# discharge-tsmp.net
KiCad netlist of a schematic drawn in Altium Designer
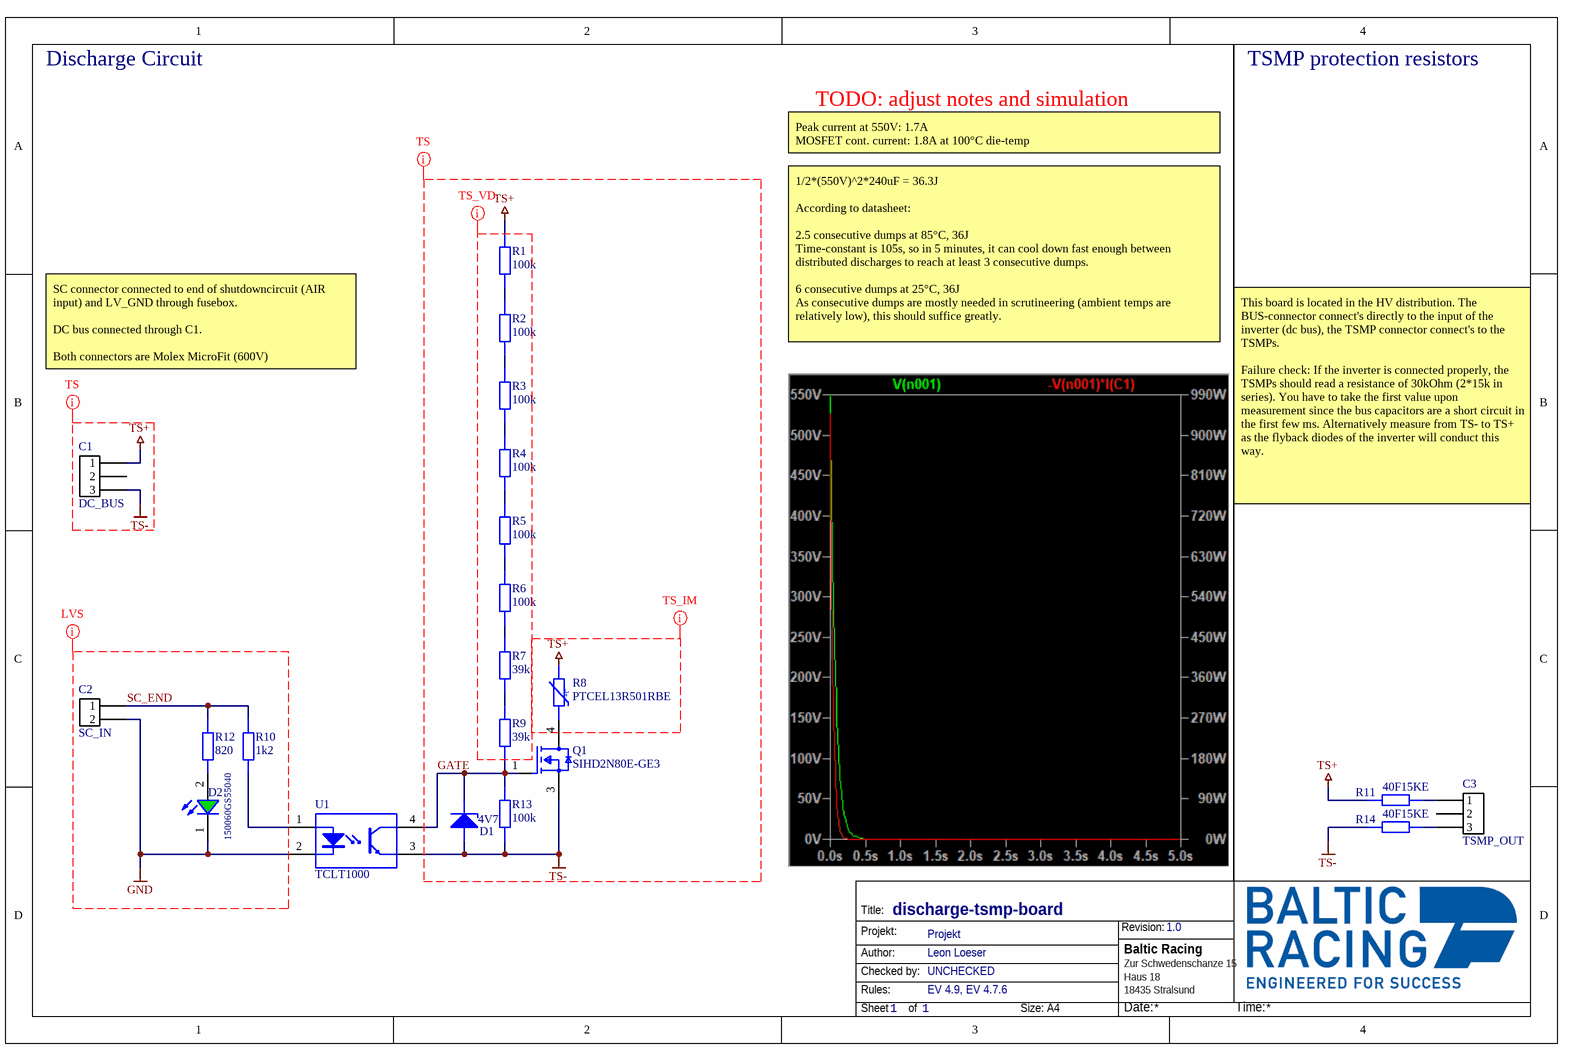
[diagram p0: discharge-tsmp.SchDoc]

(export (version "E")
  (design (tool "Eeschema 10.0.6"))
  (components
    (comp (ref "C1")
      (value "DC_BUS")
      (footprint "43650-0309")
      (description "Molex Micro-Fit 3.0 3-Pin\r\n600V\r\n8.5A")
      (libsource (lib "Standardbauteile") (part "MicroFit3.0 3-Pin"))
    )
    (comp (ref "C2")
      (value "SC_IN")
      (footprint "43650-0200")
      (description "Molex Micro-Fit 3.0 2-Pin\r\n600V\r\n8.5A")
      (libsource (lib "Standardbauteile") (part "MicroFit3.0 2-Pin"))
    )
    (comp (ref "C3")
      (value "TSMP_OUT")
      (footprint "43650-0309")
      (description "Molex Micro-Fit 3.0 3-Pin\r\n600V\r\n8.5A")
      (libsource (lib "Standardbauteile") (part "MicroFit3.0 3-Pin"))
    )
    (comp (ref "D1")
      (value "4V7")
      (footprint "SOT23")
      (libsource (lib "Standardbauteile") (part "SMD Zener Diode"))
    )
    (comp (ref "D2")
      (value "150060GS55040")
      (footprint "WL-SMCW_0603_H=0.7")
      (description "SMT Mono-color Chip LED Waterclear WL-SMCW, size 0603, Green, 3.2 V, 140 deg, 430 mcd")
      (fields (field (name "PART NUMBER") "150060GS75000") (field (name "PUBLISHER") "Wurth Elektronik"))
      (libsource (lib "ALTIUM-WL-SMCW-rev18c") (part "150060GS75000"))
    )
    (comp (ref "Q1")
      (value "SIHD2N80E-GE3")
      (footprint "FP-T16-0236-MFG")
      (description "MOSFET N-CH 800V 2.8A DPAK")
      (fields
        (field (name "MANUFACTURER") "Vishay")
        (field (name "OCTOPART") "https://octopart.com/sihd2n80e-ge3-vishay-84840963")
      )
      (libsource (lib "Altium Content Vault") (part "86656c45bbbddc162aead764a772c09"))
    )
    (comp (ref "R1")
      (value "100k")
      (footprint "STACKPOLE CSR1206")
      (description "Resistor with multiple footprints")
      (fields (field (name "Comment") "SMD Resistor"))
      (libsource (lib "Standardbauteile") (part "SMD Resistor"))
    )
    (comp (ref "R2")
      (value "100k")
      (footprint "STACKPOLE CSR1206")
      (description "Resistor with multiple footprints")
      (fields (field (name "Comment") "SMD Resistor"))
      (libsource (lib "Standardbauteile") (part "SMD Resistor"))
    )
    (comp (ref "R3")
      (value "100k")
      (footprint "STACKPOLE CSR1206")
      (description "Resistor with multiple footprints")
      (fields (field (name "Comment") "SMD Resistor"))
      (libsource (lib "Standardbauteile") (part "SMD Resistor"))
    )
    (comp (ref "R4")
      (value "100k")
      (footprint "STACKPOLE CSR1206")
      (description "Resistor with multiple footprints")
      (fields (field (name "Comment") "SMD Resistor"))
      (libsource (lib "Standardbauteile") (part "SMD Resistor"))
    )
    (comp (ref "R5")
      (value "100k")
      (footprint "STACKPOLE CSR1206")
      (description "Resistor with multiple footprints")
      (fields (field (name "Comment") "SMD Resistor"))
      (libsource (lib "Standardbauteile") (part "SMD Resistor"))
    )
    (comp (ref "R6")
      (value "100k")
      (footprint "STACKPOLE CSR1206")
      (description "Resistor with multiple footprints")
      (fields (field (name "Comment") "SMD Resistor"))
      (libsource (lib "Standardbauteile") (part "SMD Resistor"))
    )
    (comp (ref "R7")
      (value "39k")
      (footprint "STACKPOLE CSR1206")
      (description "Resistor with multiple footprints")
      (fields (field (name "Comment") "SMD Resistor"))
      (libsource (lib "Standardbauteile") (part "SMD Resistor"))
    )
    (comp (ref "R8")
      (value "PTCEL13R501RBE")
      (footprint "PTCEL13_H")
      (description "PTC Thermistors, Inrush Current Limiter and Energy Load-Dump\r\n\r\n500Ohm, 150J")
      (fields (field (name "MANUFACTURER") "Vishay"))
      (libsource (lib "Leon") (part "PTCEL13R501RBE"))
    )
    (comp (ref "R9")
      (value "39k")
      (footprint "STACKPOLE CSR1206")
      (description "Resistor with multiple footprints")
      (fields (field (name "Comment") "SMD Resistor"))
      (libsource (lib "Standardbauteile") (part "SMD Resistor"))
    )
    (comp (ref "R10")
      (value "1k2")
      (footprint "STACKPOLE CSR0603")
      (description "Resistor with multiple footprints")
      (fields (field (name "Comment") "SMD Resistor"))
      (libsource (lib "Standardbauteile") (part "SMD Resistor"))
    )
    (comp (ref "R11")
      (value "40F15KE")
      (footprint "OHMITE_40_SERIES")
      (description "Wirewound Resistors 10watt 15K 1% Axial")
      (fields (field (name "MANUFACTURER") "Ohmite") (field (name "TOLERANCE") "1%"))
      (libsource (lib "Leon") (part "40F15KE"))
    )
    (comp (ref "R12")
      (value "820")
      (footprint "STACKPOLE CSR0603")
      (description "Resistor with multiple footprints")
      (fields (field (name "Comment") "SMD Resistor"))
      (libsource (lib "Standardbauteile") (part "SMD Resistor"))
    )
    (comp (ref "R13")
      (value "100k")
      (footprint "STACKPOLE CSR0603")
      (description "Resistor with multiple footprints")
      (fields (field (name "Comment") "SMD Resistor"))
      (libsource (lib "Standardbauteile") (part "SMD Resistor"))
    )
    (comp (ref "R14")
      (value "40F15KE")
      (footprint "OHMITE_40_SERIES")
      (description "Wirewound Resistors 10watt 15K 1% Axial")
      (fields (field (name "MANUFACTURER") "Ohmite") (field (name "TOLERANCE") "1%"))
      (libsource (lib "Leon") (part "40F15KE"))
    )
    (comp (ref "U1")
      (value "TCLT1000")
      (footprint "VISH-SOP4L-4_V")
      (fields (field (name "MANUFACTURER") "Vishay/Semiconductor"))
      (libsource (lib "Altium Content Vault") (part "OPTO-ACEC-4"))
    )
  )
  (nets
    (net (code "1") (name "/GATE") (class "Default")
      (node (ref "D1") (pin "C") (pinfunction "C_C") (pintype "passive"))
      (node (ref "Q1") (pin "1") (pinfunction "G_1") (pintype "passive"))
      (node (ref "R13") (pin "2") (pinfunction "2_2") (pintype "passive"))
      (node (ref "R9") (pin "1") (pinfunction "1_1") (pintype "passive"))
      (node (ref "U1") (pin "4") (pinfunction "C_4") (pintype "passive"))
    )
    (net (code "2") (name "/SC_END") (class "Default")
      (node (ref "C2") (pin "1") (pinfunction "1_1") (pintype "passive"))
      (node (ref "R10") (pin "1") (pinfunction "1_1") (pintype "passive"))
      (node (ref "R12") (pin "2") (pinfunction "2_2") (pintype "passive"))
    )
    (net (code "3") (name "GND") (class "Default")
      (node (ref "C2") (pin "2") (pinfunction "2_2") (pintype "passive"))
      (node (ref "D2") (pin "1") (pinfunction "K_1") (pintype "passive"))
      (node (ref "U1") (pin "2") (pinfunction "C_2") (pintype "passive"))
    )
    (net (code "4") (name "Net-(C3-Pad1)") (class "Default")
      (node (ref "C3") (pin "1") (pinfunction "1_1") (pintype "passive"))
      (node (ref "R11") (pin "2") (pinfunction "2_2") (pintype "passive"))
    )
    (net (code "5") (name "Net-(C3-Pad3)") (class "Default")
      (node (ref "C3") (pin "3") (pinfunction "3_3") (pintype "passive"))
      (node (ref "R14") (pin "2") (pinfunction "2_2") (pintype "passive"))
    )
    (net (code "6") (name "Net-(D2-A)") (class "Default")
      (node (ref "D2") (pin "2") (pinfunction "A_2") (pintype "passive"))
      (node (ref "R12") (pin "1") (pinfunction "1_1") (pintype "passive"))
    )
    (net (code "7") (name "Net-(Q1-D)") (class "Default")
      (node (ref "Q1") (pin "4") (pinfunction "D_4") (pintype "passive"))
      (node (ref "R8") (pin "2") (pinfunction "2_2") (pintype "passive"))
    )
    (net (code "8") (name "Net-(R1-Pad1)") (class "Default")
      (node (ref "R1") (pin "1") (pinfunction "1_1") (pintype "passive"))
      (node (ref "R2") (pin "2") (pinfunction "2_2") (pintype "passive"))
    )
    (net (code "9") (name "Net-(R2-Pad1)") (class "Default")
      (node (ref "R2") (pin "1") (pinfunction "1_1") (pintype "passive"))
      (node (ref "R3") (pin "2") (pinfunction "2_2") (pintype "passive"))
    )
    (net (code "10") (name "Net-(R3-Pad1)") (class "Default")
      (node (ref "R3") (pin "1") (pinfunction "1_1") (pintype "passive"))
      (node (ref "R4") (pin "2") (pinfunction "2_2") (pintype "passive"))
    )
    (net (code "11") (name "Net-(R4-Pad1)") (class "Default")
      (node (ref "R4") (pin "1") (pinfunction "1_1") (pintype "passive"))
      (node (ref "R5") (pin "2") (pinfunction "2_2") (pintype "passive"))
    )
    (net (code "12") (name "Net-(R5-Pad1)") (class "Default")
      (node (ref "R5") (pin "1") (pinfunction "1_1") (pintype "passive"))
      (node (ref "R6") (pin "2") (pinfunction "2_2") (pintype "passive"))
    )
    (net (code "13") (name "Net-(R6-Pad1)") (class "Default")
      (node (ref "R6") (pin "1") (pinfunction "1_1") (pintype "passive"))
      (node (ref "R7") (pin "2") (pinfunction "2_2") (pintype "passive"))
    )
    (net (code "14") (name "Net-(R7-Pad1)") (class "Default")
      (node (ref "R7") (pin "1") (pinfunction "1_1") (pintype "passive"))
      (node (ref "R9") (pin "2") (pinfunction "2_2") (pintype "passive"))
    )
    (net (code "15") (name "Net-(U1-A)") (class "Default")
      (node (ref "R10") (pin "2") (pinfunction "2_2") (pintype "passive"))
      (node (ref "U1") (pin "1") (pinfunction "A_1") (pintype "passive"))
    )
    (net (code "16") (name "TS+") (class "Default")
      (node (ref "C1") (pin "1") (pinfunction "1_1") (pintype "passive"))
      (node (ref "R1") (pin "2") (pinfunction "2_2") (pintype "passive"))
      (node (ref "R11") (pin "1") (pinfunction "1_1") (pintype "passive"))
      (node (ref "R8") (pin "1") (pinfunction "1_1") (pintype "passive"))
    )
    (net (code "17") (name "TS-") (class "Default")
      (node (ref "C1") (pin "3") (pinfunction "3_3") (pintype "passive"))
      (node (ref "D1") (pin "A") (pinfunction "A_A") (pintype "passive"))
      (node (ref "Q1") (pin "3") (pinfunction "S_3") (pintype "passive"))
      (node (ref "R13") (pin "1") (pinfunction "1_1") (pintype "passive"))
      (node (ref "R14") (pin "1") (pinfunction "1_1") (pintype "passive"))
      (node (ref "U1") (pin "3") (pinfunction "E_3") (pintype "passive"))
    )
    (net (code "18") (name "unconnected-(C1-Pad2)") (class "Default")
      (node (ref "C1") (pin "2") (pinfunction "2_2") (pintype "passive"))
    )
    (net (code "19") (name "unconnected-(C3-Pad2)") (class "Default")
      (node (ref "C3") (pin "2") (pinfunction "2_2") (pintype "passive"))
    )
  )
)
